# DisplayUnit.net
KiCad netlist of a schematic drawn in Altium Designer
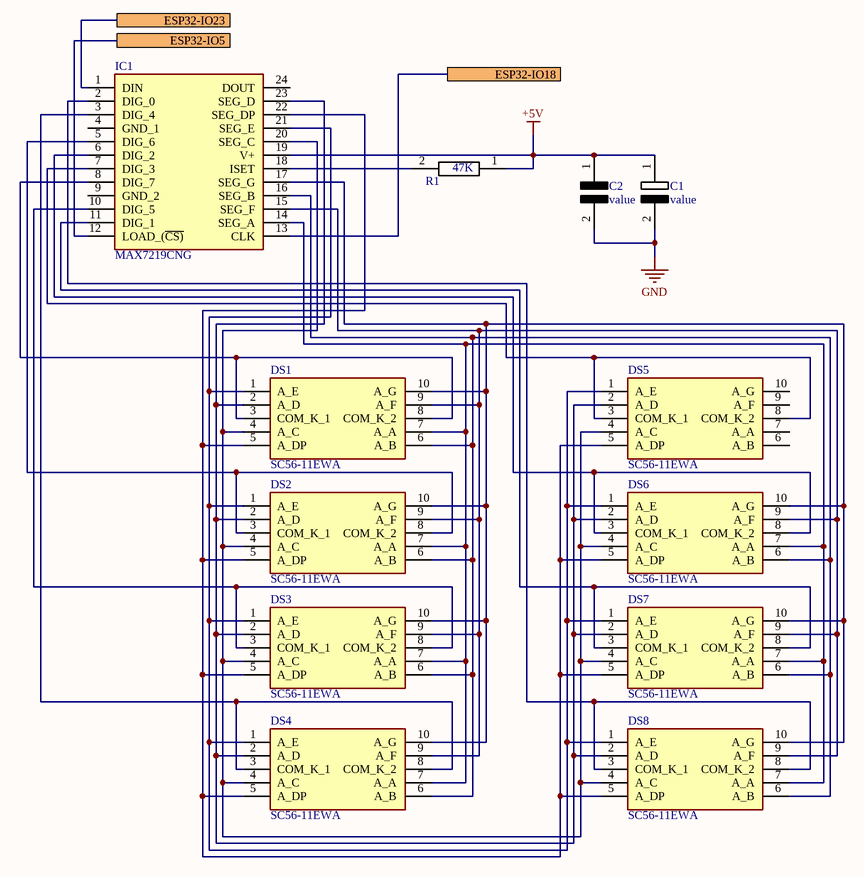
[diagram p0: DisplayUnit.SchDoc]

(export (version "E")
  (design (tool "Eeschema 10.0.6"))
  (components
    (comp (ref "C1")
      (value "value")
      (footprint "C0805")
      (description "0805 ceramic capacitor")
      (fields
        (field (name "MANUFACTURER_PART_NUMBER") "GRM188R71H103KA01D")
        (field (name "MOUSER PART NUMBER") "81-GRM39X103K50D")
      )
      (libsource (lib "Schlib1") (part "elektrolytischeC0805"))
    )
    (comp (ref "C2")
      (value "value")
      (footprint "C0805")
      (description "0805 ceramic capacitor")
      (fields
        (field (name "MANUFACTURER_PART_NUMBER") "GRM188R71H103KA01D")
        (field (name "MOUSER PART NUMBER") "81-GRM39X103K50D")
      )
      (libsource (lib "Schlib1") (part "KeramischeC0805_1"))
    )
    (comp (ref "DS1")
      (value "SC56-11EWA")
      (footprint "SamacSys:DIPS1524W75P254L1270H825Q10N")
      (description "Display")
      (fields (field (name "MOUSER PART NUMBER") "604-SC56-11EWA"))
      (libsource (lib "Schlib1") (part "SC56-11EWA"))
    )
    (comp (ref "DS2")
      (value "SC56-11EWA")
      (footprint "SamacSys:DIPS1524W75P254L1270H825Q10N")
      (description "Display")
      (fields (field (name "MOUSER PART NUMBER") "604-SC56-11EWA"))
      (libsource (lib "Schlib1") (part "SC56-11EWA"))
    )
    (comp (ref "DS3")
      (value "SC56-11EWA")
      (footprint "SamacSys:DIPS1524W75P254L1270H825Q10N")
      (description "Display")
      (fields (field (name "MOUSER PART NUMBER") "604-SC56-11EWA"))
      (libsource (lib "Schlib1") (part "SC56-11EWA"))
    )
    (comp (ref "DS4")
      (value "SC56-11EWA")
      (footprint "SamacSys:DIPS1524W75P254L1270H825Q10N")
      (description "Display")
      (fields (field (name "MOUSER PART NUMBER") "604-SC56-11EWA"))
      (libsource (lib "Schlib1") (part "SC56-11EWA"))
    )
    (comp (ref "DS5")
      (value "SC56-11EWA")
      (footprint "SamacSys:DIPS1524W75P254L1270H825Q10N")
      (description "Display")
      (fields (field (name "MOUSER PART NUMBER") "604-SC56-11EWA"))
      (libsource (lib "Schlib1") (part "SC56-11EWA"))
    )
    (comp (ref "DS6")
      (value "SC56-11EWA")
      (footprint "SamacSys:DIPS1524W75P254L1270H825Q10N")
      (description "Display")
      (fields (field (name "MOUSER PART NUMBER") "604-SC56-11EWA"))
      (libsource (lib "Schlib1") (part "SC56-11EWA"))
    )
    (comp (ref "DS7")
      (value "SC56-11EWA")
      (footprint "SamacSys:DIPS1524W75P254L1270H825Q10N")
      (description "Display")
      (fields (field (name "MOUSER PART NUMBER") "604-SC56-11EWA"))
      (libsource (lib "Schlib1") (part "SC56-11EWA"))
    )
    (comp (ref "DS8")
      (value "SC56-11EWA")
      (footprint "SamacSys:DIPS1524W75P254L1270H825Q10N")
      (description "Display")
      (fields (field (name "MOUSER PART NUMBER") "604-SC56-11EWA"))
      (libsource (lib "Schlib1") (part "SC56-11EWA"))
    )
    (comp (ref "IC1")
      (value "MAX7219CNG")
      (footprint "SamacSys:DIP794W56P254L3054H457Q24N")
      (description "Integrated Circuit")
      (fields (field (name "MOUSER PART NUMBER") "700-MAX7219CNG-NR"))
      (libsource (lib "Schlib1") (part "MAX7219CNG"))
    )
    (comp (ref "R1")
      (value "47K")
      (footprint "SamacSys:RESC2012X60N")
      (description "Resistor0805")
      (fields
        (field (name "MANUFACTURER_PART_NUMBER") "CRCW08050000Z0EAHP")
        (field (name "MOUSER PART NUMBER") "71-CRCW08050000Z0EAH")
      )
      (libsource (lib "Schlib1") (part "Resistor0805"))
    )
  )
  (nets
    (net (code "1") (name "+5V") (class "Default")
      (node (ref "C1") (pin "1") (pinfunction "1_1") (pintype "passive"))
      (node (ref "C2") (pin "1") (pinfunction "1_1") (pintype "passive"))
      (node (ref "IC1") (pin "19") (pinfunction "V+_19") (pintype "passive"))
      (node (ref "R1") (pin "1") (pinfunction "1_1") (pintype "passive"))
    )
    (net (code "2") (name "/ESP32-IO5") (class "Default")
      (node (ref "IC1") (pin "12") (pinfunction "LOAD_(~{CS)}_12") (pintype "passive"))
    )
    (net (code "3") (name "/ESP32-IO18") (class "Default")
      (node (ref "IC1") (pin "13") (pinfunction "CLK_13") (pintype "passive"))
    )
    (net (code "4") (name "/ESP32-IO23") (class "Default")
      (node (ref "IC1") (pin "1") (pinfunction "DIN_1") (pintype "passive"))
    )
    (net (code "5") (name "GND") (class "Default")
      (node (ref "C1") (pin "2") (pinfunction "2_2") (pintype "passive"))
      (node (ref "C2") (pin "2") (pinfunction "2_2") (pintype "passive"))
    )
    (net (code "6") (name "Net-(DS1-A_A)") (class "Default")
      (node (ref "DS1") (pin "7") (pinfunction "A_A_7") (pintype "passive"))
      (node (ref "DS2") (pin "7") (pinfunction "A_A_7") (pintype "passive"))
      (node (ref "DS3") (pin "7") (pinfunction "A_A_7") (pintype "passive"))
      (node (ref "DS4") (pin "7") (pinfunction "A_A_7") (pintype "passive"))
      (node (ref "DS6") (pin "7") (pinfunction "A_A_7") (pintype "passive"))
      (node (ref "DS7") (pin "7") (pinfunction "A_A_7") (pintype "passive"))
      (node (ref "DS8") (pin "7") (pinfunction "A_A_7") (pintype "passive"))
      (node (ref "IC1") (pin "14") (pinfunction "SEG_A_14") (pintype "passive"))
    )
    (net (code "7") (name "Net-(DS1-A_B)") (class "Default")
      (node (ref "DS1") (pin "6") (pinfunction "A_B_6") (pintype "passive"))
      (node (ref "DS2") (pin "6") (pinfunction "A_B_6") (pintype "passive"))
      (node (ref "DS3") (pin "6") (pinfunction "A_B_6") (pintype "passive"))
      (node (ref "DS4") (pin "6") (pinfunction "A_B_6") (pintype "passive"))
      (node (ref "DS6") (pin "6") (pinfunction "A_B_6") (pintype "passive"))
      (node (ref "DS7") (pin "6") (pinfunction "A_B_6") (pintype "passive"))
      (node (ref "DS8") (pin "6") (pinfunction "A_B_6") (pintype "passive"))
      (node (ref "IC1") (pin "16") (pinfunction "SEG_B_16") (pintype "passive"))
    )
    (net (code "8") (name "Net-(DS1-A_C)") (class "Default")
      (node (ref "DS1") (pin "4") (pinfunction "A_C_4") (pintype "passive"))
      (node (ref "DS2") (pin "4") (pinfunction "A_C_4") (pintype "passive"))
      (node (ref "DS3") (pin "4") (pinfunction "A_C_4") (pintype "passive"))
      (node (ref "DS4") (pin "4") (pinfunction "A_C_4") (pintype "passive"))
      (node (ref "DS5") (pin "4") (pinfunction "A_C_4") (pintype "passive"))
      (node (ref "DS6") (pin "4") (pinfunction "A_C_4") (pintype "passive"))
      (node (ref "DS7") (pin "4") (pinfunction "A_C_4") (pintype "passive"))
      (node (ref "DS8") (pin "4") (pinfunction "A_C_4") (pintype "passive"))
      (node (ref "IC1") (pin "20") (pinfunction "SEG_C_20") (pintype "passive"))
    )
    (net (code "9") (name "Net-(DS1-A_D)") (class "Default")
      (node (ref "DS1") (pin "2") (pinfunction "A_D_2") (pintype "passive"))
      (node (ref "DS2") (pin "2") (pinfunction "A_D_2") (pintype "passive"))
      (node (ref "DS3") (pin "2") (pinfunction "A_D_2") (pintype "passive"))
      (node (ref "DS4") (pin "2") (pinfunction "A_D_2") (pintype "passive"))
      (node (ref "DS5") (pin "2") (pinfunction "A_D_2") (pintype "passive"))
      (node (ref "DS6") (pin "2") (pinfunction "A_D_2") (pintype "passive"))
      (node (ref "DS7") (pin "2") (pinfunction "A_D_2") (pintype "passive"))
      (node (ref "DS8") (pin "2") (pinfunction "A_D_2") (pintype "passive"))
      (node (ref "IC1") (pin "23") (pinfunction "SEG_D_23") (pintype "passive"))
    )
    (net (code "10") (name "Net-(DS1-A_DP)") (class "Default")
      (node (ref "DS1") (pin "5") (pinfunction "A_DP_5") (pintype "passive"))
      (node (ref "DS2") (pin "5") (pinfunction "A_DP_5") (pintype "passive"))
      (node (ref "DS3") (pin "5") (pinfunction "A_DP_5") (pintype "passive"))
      (node (ref "DS4") (pin "5") (pinfunction "A_DP_5") (pintype "passive"))
      (node (ref "DS5") (pin "5") (pinfunction "A_DP_5") (pintype "passive"))
      (node (ref "DS6") (pin "5") (pinfunction "A_DP_5") (pintype "passive"))
      (node (ref "DS7") (pin "5") (pinfunction "A_DP_5") (pintype "passive"))
      (node (ref "DS8") (pin "5") (pinfunction "A_DP_5") (pintype "passive"))
      (node (ref "IC1") (pin "22") (pinfunction "SEG_DP_22") (pintype "passive"))
    )
    (net (code "11") (name "Net-(DS1-A_E)") (class "Default")
      (node (ref "DS1") (pin "1") (pinfunction "A_E_1") (pintype "passive"))
      (node (ref "DS2") (pin "1") (pinfunction "A_E_1") (pintype "passive"))
      (node (ref "DS3") (pin "1") (pinfunction "A_E_1") (pintype "passive"))
      (node (ref "DS4") (pin "1") (pinfunction "A_E_1") (pintype "passive"))
      (node (ref "DS5") (pin "1") (pinfunction "A_E_1") (pintype "passive"))
      (node (ref "DS6") (pin "1") (pinfunction "A_E_1") (pintype "passive"))
      (node (ref "DS7") (pin "1") (pinfunction "A_E_1") (pintype "passive"))
      (node (ref "DS8") (pin "1") (pinfunction "A_E_1") (pintype "passive"))
      (node (ref "IC1") (pin "21") (pinfunction "SEG_E_21") (pintype "passive"))
    )
    (net (code "12") (name "Net-(DS1-A_F)") (class "Default")
      (node (ref "DS1") (pin "9") (pinfunction "A_F_9") (pintype "passive"))
      (node (ref "DS2") (pin "9") (pinfunction "A_F_9") (pintype "passive"))
      (node (ref "DS3") (pin "9") (pinfunction "A_F_9") (pintype "passive"))
      (node (ref "DS4") (pin "9") (pinfunction "A_F_9") (pintype "passive"))
      (node (ref "DS6") (pin "9") (pinfunction "A_F_9") (pintype "passive"))
      (node (ref "DS7") (pin "9") (pinfunction "A_F_9") (pintype "passive"))
      (node (ref "DS8") (pin "9") (pinfunction "A_F_9") (pintype "passive"))
      (node (ref "IC1") (pin "15") (pinfunction "SEG_F_15") (pintype "passive"))
    )
    (net (code "13") (name "Net-(DS1-A_G)") (class "Default")
      (node (ref "DS1") (pin "10") (pinfunction "A_G_10") (pintype "passive"))
      (node (ref "DS2") (pin "10") (pinfunction "A_G_10") (pintype "passive"))
      (node (ref "DS3") (pin "10") (pinfunction "A_G_10") (pintype "passive"))
      (node (ref "DS4") (pin "10") (pinfunction "A_G_10") (pintype "passive"))
      (node (ref "DS6") (pin "10") (pinfunction "A_G_10") (pintype "passive"))
      (node (ref "DS7") (pin "10") (pinfunction "A_G_10") (pintype "passive"))
      (node (ref "DS8") (pin "10") (pinfunction "A_G_10") (pintype "passive"))
      (node (ref "IC1") (pin "17") (pinfunction "SEG_G_17") (pintype "passive"))
    )
    (net (code "14") (name "Net-(DS1-COM_K_1)") (class "Default")
      (node (ref "DS1") (pin "3") (pinfunction "COM_K_1_3") (pintype "passive"))
      (node (ref "DS1") (pin "8") (pinfunction "COM_K_2_8") (pintype "passive"))
      (node (ref "IC1") (pin "8") (pinfunction "DIG_7_8") (pintype "passive"))
    )
    (net (code "15") (name "Net-(DS2-COM_K_1)") (class "Default")
      (node (ref "DS2") (pin "3") (pinfunction "COM_K_1_3") (pintype "passive"))
      (node (ref "DS2") (pin "8") (pinfunction "COM_K_2_8") (pintype "passive"))
      (node (ref "IC1") (pin "5") (pinfunction "DIG_6_5") (pintype "passive"))
    )
    (net (code "16") (name "Net-(DS3-COM_K_1)") (class "Default")
      (node (ref "DS3") (pin "3") (pinfunction "COM_K_1_3") (pintype "passive"))
      (node (ref "DS3") (pin "8") (pinfunction "COM_K_2_8") (pintype "passive"))
      (node (ref "IC1") (pin "10") (pinfunction "DIG_5_10") (pintype "passive"))
    )
    (net (code "17") (name "Net-(DS4-COM_K_1)") (class "Default")
      (node (ref "DS4") (pin "3") (pinfunction "COM_K_1_3") (pintype "passive"))
      (node (ref "DS4") (pin "8") (pinfunction "COM_K_2_8") (pintype "passive"))
      (node (ref "IC1") (pin "3") (pinfunction "DIG_4_3") (pintype "passive"))
    )
    (net (code "18") (name "Net-(DS5-COM_K_1)") (class "Default")
      (node (ref "DS5") (pin "3") (pinfunction "COM_K_1_3") (pintype "passive"))
      (node (ref "DS5") (pin "8") (pinfunction "COM_K_2_8") (pintype "passive"))
      (node (ref "IC1") (pin "7") (pinfunction "DIG_3_7") (pintype "passive"))
    )
    (net (code "19") (name "Net-(DS6-COM_K_1)") (class "Default")
      (node (ref "DS6") (pin "3") (pinfunction "COM_K_1_3") (pintype "passive"))
      (node (ref "DS6") (pin "8") (pinfunction "COM_K_2_8") (pintype "passive"))
      (node (ref "IC1") (pin "6") (pinfunction "DIG_2_6") (pintype "passive"))
    )
    (net (code "20") (name "Net-(DS7-COM_K_1)") (class "Default")
      (node (ref "DS7") (pin "3") (pinfunction "COM_K_1_3") (pintype "passive"))
      (node (ref "DS7") (pin "8") (pinfunction "COM_K_2_8") (pintype "passive"))
      (node (ref "IC1") (pin "11") (pinfunction "DIG_1_11") (pintype "passive"))
    )
    (net (code "21") (name "Net-(DS8-COM_K_1)") (class "Default")
      (node (ref "DS8") (pin "3") (pinfunction "COM_K_1_3") (pintype "passive"))
      (node (ref "DS8") (pin "8") (pinfunction "COM_K_2_8") (pintype "passive"))
      (node (ref "IC1") (pin "2") (pinfunction "DIG_0_2") (pintype "passive"))
    )
    (net (code "22") (name "Net-(IC1-ISET)") (class "Default")
      (node (ref "IC1") (pin "18") (pinfunction "ISET_18") (pintype "passive"))
      (node (ref "R1") (pin "2") (pinfunction "2_2") (pintype "passive"))
    )
    (net (code "23") (name "unconnected-(DS5-A_A-Pad7)") (class "Default")
      (node (ref "DS5") (pin "7") (pinfunction "A_A_7") (pintype "passive"))
    )
    (net (code "24") (name "unconnected-(DS5-A_B-Pad6)") (class "Default")
      (node (ref "DS5") (pin "6") (pinfunction "A_B_6") (pintype "passive"))
    )
    (net (code "25") (name "unconnected-(DS5-A_F-Pad9)") (class "Default")
      (node (ref "DS5") (pin "9") (pinfunction "A_F_9") (pintype "passive"))
    )
    (net (code "26") (name "unconnected-(DS5-A_G-Pad10)") (class "Default")
      (node (ref "DS5") (pin "10") (pinfunction "A_G_10") (pintype "passive"))
    )
    (net (code "27") (name "unconnected-(IC1-DOUT-Pad24)") (class "Default")
      (node (ref "IC1") (pin "24") (pinfunction "DOUT_24") (pintype "passive"))
    )
    (net (code "28") (name "unconnected-(IC1-GND_1-Pad4)") (class "Default")
      (node (ref "IC1") (pin "4") (pinfunction "GND_1_4") (pintype "passive"))
    )
    (net (code "29") (name "unconnected-(IC1-GND_2-Pad9)") (class "Default")
      (node (ref "IC1") (pin "9") (pinfunction "GND_2_9") (pintype "passive"))
    )
  )
)
